# Power.net
KiCad netlist of a schematic drawn in Altium Designer
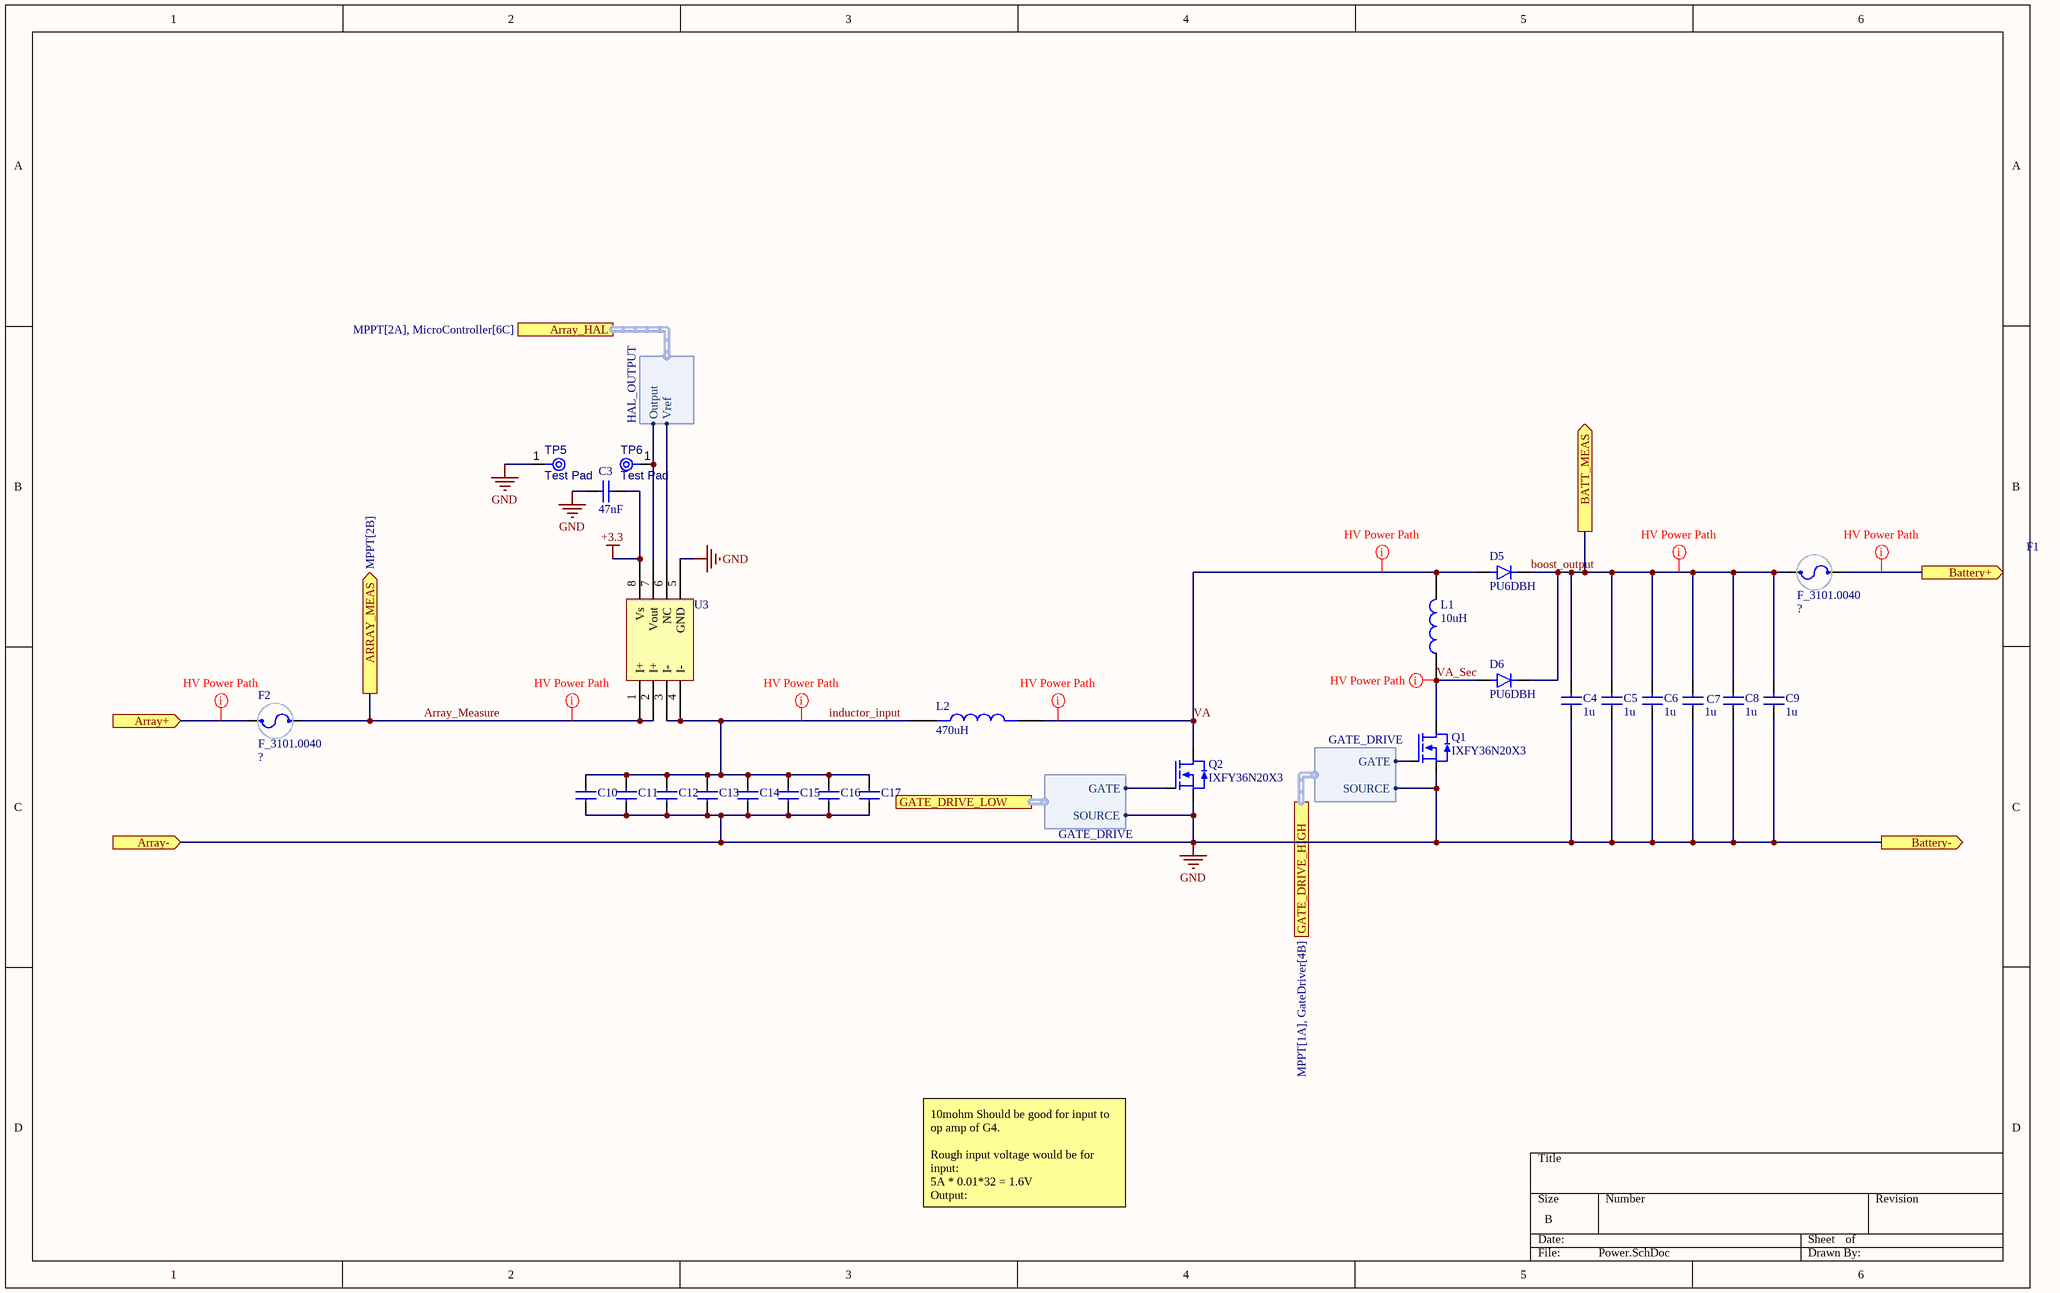
[diagram p0: Power.SchDoc]

(export (version "E")
  (design (tool "Eeschema 10.0.6"))
  (components
    (comp (ref "C3")
      (value "47nF")
      (footprint "0603_CAPACITOR")
      (fields (field (name "TOLERANCE") "10%") (field (name "Comment") "C0603C473K4RECAUTO"))
      (libsource (lib "University of Minnesota - Solar Vehicle Project") (part "Cap"))
    )
    (comp (ref "C4")
      (value "1u")
      (footprint "1812_Capacitor")
      (description "Cap Cer 1UF 200V X7R 1812")
      (fields (field (name "Comment") "KGM43JR72D105JV"))
      (libsource (lib "University of Minnesota - Solar Vehicle Project") (part "C_102R18W472KV4E"))
    )
    (comp (ref "C5")
      (value "1u")
      (footprint "1812_Capacitor")
      (description "Cap Cer 1UF 200V X7R 1812")
      (fields (field (name "Comment") "KGM43JR72D105JV"))
      (libsource (lib "University of Minnesota - Solar Vehicle Project") (part "C_102R18W472KV4E"))
    )
    (comp (ref "C6")
      (value "1u")
      (footprint "1812_Capacitor")
      (description "Cap Cer 1UF 200V X7R 1812")
      (fields (field (name "Comment") "KGM43JR72D105JV"))
      (libsource (lib "University of Minnesota - Solar Vehicle Project") (part "C_102R18W472KV4E"))
    )
    (comp (ref "C7")
      (value "1u")
      (footprint "1812_Capacitor")
      (description "Cap Cer 1UF 200V X7R 1812")
      (fields (field (name "Comment") "KGM43JR72D105JV"))
      (libsource (lib "University of Minnesota - Solar Vehicle Project") (part "C_102R18W472KV4E"))
    )
    (comp (ref "C8")
      (value "1u")
      (footprint "1812_Capacitor")
      (description "Cap Cer 1UF 200V X7R 1812")
      (fields (field (name "Comment") "KGM43JR72D105JV"))
      (libsource (lib "University of Minnesota - Solar Vehicle Project") (part "C_102R18W472KV4E"))
    )
    (comp (ref "C9")
      (value "1u")
      (footprint "1812_Capacitor")
      (description "Cap Cer 1UF 200V X7R 1812")
      (fields (field (name "Comment") "KGM43JR72D105JV"))
      (libsource (lib "University of Minnesota - Solar Vehicle Project") (part "C_102R18W472KV4E"))
    )
    (comp (ref "C10")
      (value "HMK432BJ105MM-T")
      (footprint "1812_Capacitor")
      (description "Medium-High Voltage Multilayer Ceramic Capacitors, 100V, 1 uF, ± 20 %, 1812, X5R/B, RoHS")
      (libsource (lib "University of Minnesota - Solar Vehicle Project") (part "C_102R18W472KV4E"))
    )
    (comp (ref "C11")
      (value "HMK432BJ105MM-T")
      (footprint "1812_Capacitor")
      (description "Medium-High Voltage Multilayer Ceramic Capacitors, 100V, 1 uF, ± 20 %, 1812, X5R/B, RoHS")
      (libsource (lib "University of Minnesota - Solar Vehicle Project") (part "C_102R18W472KV4E"))
    )
    (comp (ref "C12")
      (value "HMK432BJ105MM-T")
      (footprint "1812_Capacitor")
      (description "Medium-High Voltage Multilayer Ceramic Capacitors, 100V, 1 uF, ± 20 %, 1812, X5R/B, RoHS")
      (libsource (lib "University of Minnesota - Solar Vehicle Project") (part "C_102R18W472KV4E"))
    )
    (comp (ref "C13")
      (value "HMK432BJ105MM-T")
      (footprint "1812_Capacitor")
      (description "Medium-High Voltage Multilayer Ceramic Capacitors, 100V, 1 uF, ± 20 %, 1812, X5R/B, RoHS")
      (libsource (lib "University of Minnesota - Solar Vehicle Project") (part "C_102R18W472KV4E"))
    )
    (comp (ref "C14")
      (value "HMK432BJ105MM-T")
      (footprint "1812_Capacitor")
      (description "Medium-High Voltage Multilayer Ceramic Capacitors, 100V, 1 uF, ± 20 %, 1812, X5R/B, RoHS")
      (libsource (lib "University of Minnesota - Solar Vehicle Project") (part "C_102R18W472KV4E"))
    )
    (comp (ref "C15")
      (value "HMK432BJ105MM-T")
      (footprint "1812_Capacitor")
      (description "Medium-High Voltage Multilayer Ceramic Capacitors, 100V, 1 uF, ± 20 %, 1812, X5R/B, RoHS")
      (libsource (lib "University of Minnesota - Solar Vehicle Project") (part "C_102R18W472KV4E"))
    )
    (comp (ref "C16")
      (value "HMK432BJ105MM-T")
      (footprint "1812_Capacitor")
      (description "Medium-High Voltage Multilayer Ceramic Capacitors, 100V, 1 uF, ± 20 %, 1812, X5R/B, RoHS")
      (libsource (lib "University of Minnesota - Solar Vehicle Project") (part "C_102R18W472KV4E"))
    )
    (comp (ref "C17")
      (value "HMK432BJ105MM-T")
      (footprint "1812_Capacitor")
      (description "Medium-High Voltage Multilayer Ceramic Capacitors, 100V, 1 uF, ± 20 %, 1812, X5R/B, RoHS")
      (libsource (lib "University of Minnesota - Solar Vehicle Project") (part "C_102R18W472KV4E"))
    )
    (comp (ref "D5")
      (value "PU6DBH")
      (footprint "DIOM4336X265N")
      (description "25ns, 6A, 200V, Ultra Fast Recovery Rectifier")
      (fields
        (field (name "MF") "Taiwan Semiconductor")
        (field (name "DIGI-KEY_PART_NUMBER") "1801-PU6DBHTR-ND")
      )
      (libsource (lib "University of Minnesota - Solar Vehicle Project") (part "PU6DBH"))
    )
    (comp (ref "D6")
      (value "PU6DBH")
      (footprint "DIOM4336X265N")
      (description "25ns, 6A, 200V, Ultra Fast Recovery Rectifier")
      (fields
        (field (name "MF") "Taiwan Semiconductor")
        (field (name "DIGI-KEY_PART_NUMBER") "1801-PU6DBHTR-ND")
      )
      (libsource (lib "University of Minnesota - Solar Vehicle Project") (part "PU6DBH"))
    )
    (comp (ref "F1")
      (value "F_3101.0040")
      (footprint "F_FPG4")
      (description "Fuse Holder 16A 500V 1 Circuit Cartridge PCB")
      (fields
        (field (name "ALTIUM_VALUE") "?")
        (field (name "MANUFACTURER PART NUMBER") "3101.0040")
        (field (name "MANUFACTURER") "Schurter")
      )
      (libsource (lib "University of Minnesota - Solar Vehicle Project") (part "F_3101.0040"))
    )
    (comp (ref "F2")
      (value "F_3101.0040")
      (footprint "F_FPG4")
      (description "Fuse Holder 16A 500V 1 Circuit Cartridge PCB")
      (fields
        (field (name "ALTIUM_VALUE") "?")
        (field (name "MANUFACTURER PART NUMBER") "3101.0040")
        (field (name "MANUFACTURER") "Schurter")
      )
      (libsource (lib "University of Minnesota - Solar Vehicle Project") (part "F_3101.0040"))
    )
    (comp (ref "L1")
      (value "10uH")
      (footprint "INDM125125X600N")
      (description "Ind Power Shielded Wirewound 10uH 20% 100KHz Ferrite 5.35A T/R")
      (fields (field (name "TOLERANCE") "20%") (field (name "Comment") "DR125-100-R"))
      (libsource (lib "University of Minnesota - Solar Vehicle Project") (part "L_SRN1060-100M"))
    )
    (comp (ref "L2")
      (value "470uH")
      (footprint "ATCA-08-471M-H-Footprint-1")
      (description "Coustom wound inductor using 79617A7 core")
      (fields (field (name "TOLERANCE") "20%") (field (name "Comment") "ATCA-08-471M-H"))
      (libsource (lib "University of Minnesota - Solar Vehicle Project") (part "ATCA-08-471M-H"))
    )
    (comp (ref "Q1")
      (value "IXFY36N20X3")
      (footprint "DPAK")
      (fields (field (name "POWER") "176W"))
      (libsource (lib "University of Minnesota - Solar Vehicle Project") (part "N-Channel MOSFET"))
    )
    (comp (ref "Q2")
      (value "IXFY36N20X3")
      (footprint "DPAK")
      (fields (field (name "POWER") "176W"))
      (libsource (lib "University of Minnesota - Solar Vehicle Project") (part "N-Channel MOSFET"))
    )
    (comp (ref "TP5")
      (value "Test Pad")
      (footprint "Test Pad-Footprint-1")
      (description "A circular test pad for soldering a wire to or spring tip if necessary")
      (libsource (lib "University of Minnesota - Solar Vehicle Project") (part "CMP-001-0001-4"))
    )
    (comp (ref "TP6")
      (value "Test Pad")
      (footprint "Test Pad-Footprint-1")
      (description "A circular test pad for soldering a wire to or spring tip if necessary")
      (libsource (lib "University of Minnesota - Solar Vehicle Project") (part "CMP-001-0001-4"))
    )
    (comp (ref "U3")
      (value "TMCS1101A2UQDRQ1")
      (footprint "SOIC127P610X173-8N")
      (description "Automotive, precision isolated current sensor with internal reference 8-SOIC -40 to 125")
      (libsource (lib "University of Minnesota - Solar Vehicle Project") (part "TMCS1101A2UQDRQ1"))
    )
  )
  (nets
    (net (code "3") (name "+3.3") (class "Default")
      (node (ref "C3") (pin "2") (pinfunction "2_2") (pintype "passive"))
      (node (ref "U3") (pin "8") (pinfunction "Vs_8") (pintype "passive"))
    )
    (net (code "4") (name "/Array+") (class "Default")
      (node (ref "F2") (pin "1") (pinfunction "1_1") (pintype "passive"))
    )
    (net (code "5") (name "/Array_Measure") (class "Default")
      (node (ref "F2") (pin "2") (pinfunction "2_2") (pintype "passive"))
      (node (ref "U3") (pin "1") (pinfunction "I+_1") (pintype "passive"))
      (node (ref "U3") (pin "2") (pinfunction "I+_2") (pintype "passive"))
    )
    (net (code "6") (name "/Battery+") (class "Default")
      (node (ref "F1") (pin "2") (pinfunction "2_2") (pintype "passive"))
    )
    (net (code "7") (name "/Output") (class "Default")
      (node (ref "TP6") (pin "1") (pinfunction "TP_1") (pintype "passive"))
      (node (ref "U3") (pin "7") (pinfunction "Vout_7") (pintype "passive"))
    )
    (net (code "8") (name "/VA") (class "Default")
      (node (ref "D5") (pin "A") (pinfunction "A_A") (pintype "passive"))
      (node (ref "L1") (pin "2") (pintype "passive"))
      (node (ref "L2") (pin "2") (pinfunction "2_2") (pintype "passive"))
      (node (ref "Q2") (pin "2") (pinfunction "DRAIN_2") (pintype "passive"))
    )
    (net (code "9") (name "/VA_Sec") (class "Default")
      (node (ref "D6") (pin "A") (pinfunction "A_A") (pintype "passive"))
      (node (ref "L1") (pin "1") (pintype "passive"))
      (node (ref "Q1") (pin "2") (pinfunction "DRAIN_2") (pintype "passive"))
    )
    (net (code "10") (name "/Vref") (class "Default")
      (node (ref "U3") (pin "6") (pinfunction "NC_6") (pintype "passive"))
    )
    (net (code "11") (name "/boost_output") (class "Default")
      (node (ref "C4") (pin "1") (pinfunction "1_1") (pintype "passive"))
      (node (ref "C5") (pin "1") (pinfunction "1_1") (pintype "passive"))
      (node (ref "C6") (pin "1") (pinfunction "1_1") (pintype "passive"))
      (node (ref "C7") (pin "1") (pinfunction "1_1") (pintype "passive"))
      (node (ref "C8") (pin "1") (pinfunction "1_1") (pintype "passive"))
      (node (ref "C9") (pin "1") (pinfunction "1_1") (pintype "passive"))
      (node (ref "D5") (pin "C") (pinfunction "K_C") (pintype "passive"))
      (node (ref "D6") (pin "C") (pinfunction "K_C") (pintype "passive"))
      (node (ref "F1") (pin "1") (pinfunction "1_1") (pintype "passive"))
    )
    (net (code "12") (name "/inductor_input") (class "Default")
      (node (ref "C10") (pin "1") (pinfunction "1_1") (pintype "passive"))
      (node (ref "C11") (pin "1") (pinfunction "1_1") (pintype "passive"))
      (node (ref "C12") (pin "1") (pinfunction "1_1") (pintype "passive"))
      (node (ref "C13") (pin "1") (pinfunction "1_1") (pintype "passive"))
      (node (ref "C14") (pin "1") (pinfunction "1_1") (pintype "passive"))
      (node (ref "C15") (pin "1") (pinfunction "1_1") (pintype "passive"))
      (node (ref "C16") (pin "1") (pinfunction "1_1") (pintype "passive"))
      (node (ref "C17") (pin "1") (pinfunction "1_1") (pintype "passive"))
      (node (ref "L2") (pin "1") (pinfunction "1_1") (pintype "passive"))
      (node (ref "U3") (pin "3") (pinfunction "I-_3") (pintype "passive"))
      (node (ref "U3") (pin "4") (pinfunction "I-_4") (pintype "passive"))
    )
    (net (code "15") (name "GND") (class "Default")
      (node (ref "C10") (pin "2") (pinfunction "2_2") (pintype "passive"))
      (node (ref "C11") (pin "2") (pinfunction "2_2") (pintype "passive"))
      (node (ref "C12") (pin "2") (pinfunction "2_2") (pintype "passive"))
      (node (ref "C13") (pin "2") (pinfunction "2_2") (pintype "passive"))
      (node (ref "C14") (pin "2") (pinfunction "2_2") (pintype "passive"))
      (node (ref "C15") (pin "2") (pinfunction "2_2") (pintype "passive"))
      (node (ref "C16") (pin "2") (pinfunction "2_2") (pintype "passive"))
      (node (ref "C17") (pin "2") (pinfunction "2_2") (pintype "passive"))
      (node (ref "C3") (pin "1") (pinfunction "1_1") (pintype "passive"))
      (node (ref "C4") (pin "2") (pinfunction "2_2") (pintype "passive"))
      (node (ref "C5") (pin "2") (pinfunction "2_2") (pintype "passive"))
      (node (ref "C6") (pin "2") (pinfunction "2_2") (pintype "passive"))
      (node (ref "C7") (pin "2") (pinfunction "2_2") (pintype "passive"))
      (node (ref "C8") (pin "2") (pinfunction "2_2") (pintype "passive"))
      (node (ref "C9") (pin "2") (pinfunction "2_2") (pintype "passive"))
      (node (ref "Q1") (pin "3") (pinfunction "SOURCE_3") (pintype "passive"))
      (node (ref "Q2") (pin "3") (pinfunction "SOURCE_3") (pintype "passive"))
      (node (ref "TP5") (pin "1") (pinfunction "TP_1") (pintype "passive"))
      (node (ref "U3") (pin "5") (pinfunction "GND_5") (pintype "passive"))
    )
    (net (code "16") (name "unconnected-(Q1-GATE-Pad1)") (class "Default")
      (node (ref "Q1") (pin "1") (pinfunction "GATE_1") (pintype "passive"))
    )
    (net (code "17") (name "unconnected-(Q2-GATE-Pad1)") (class "Default")
      (node (ref "Q2") (pin "1") (pinfunction "GATE_1") (pintype "passive"))
    )
  )
)
